# schema1.net
KiCad netlist of a schematic drawn in Altium Designer
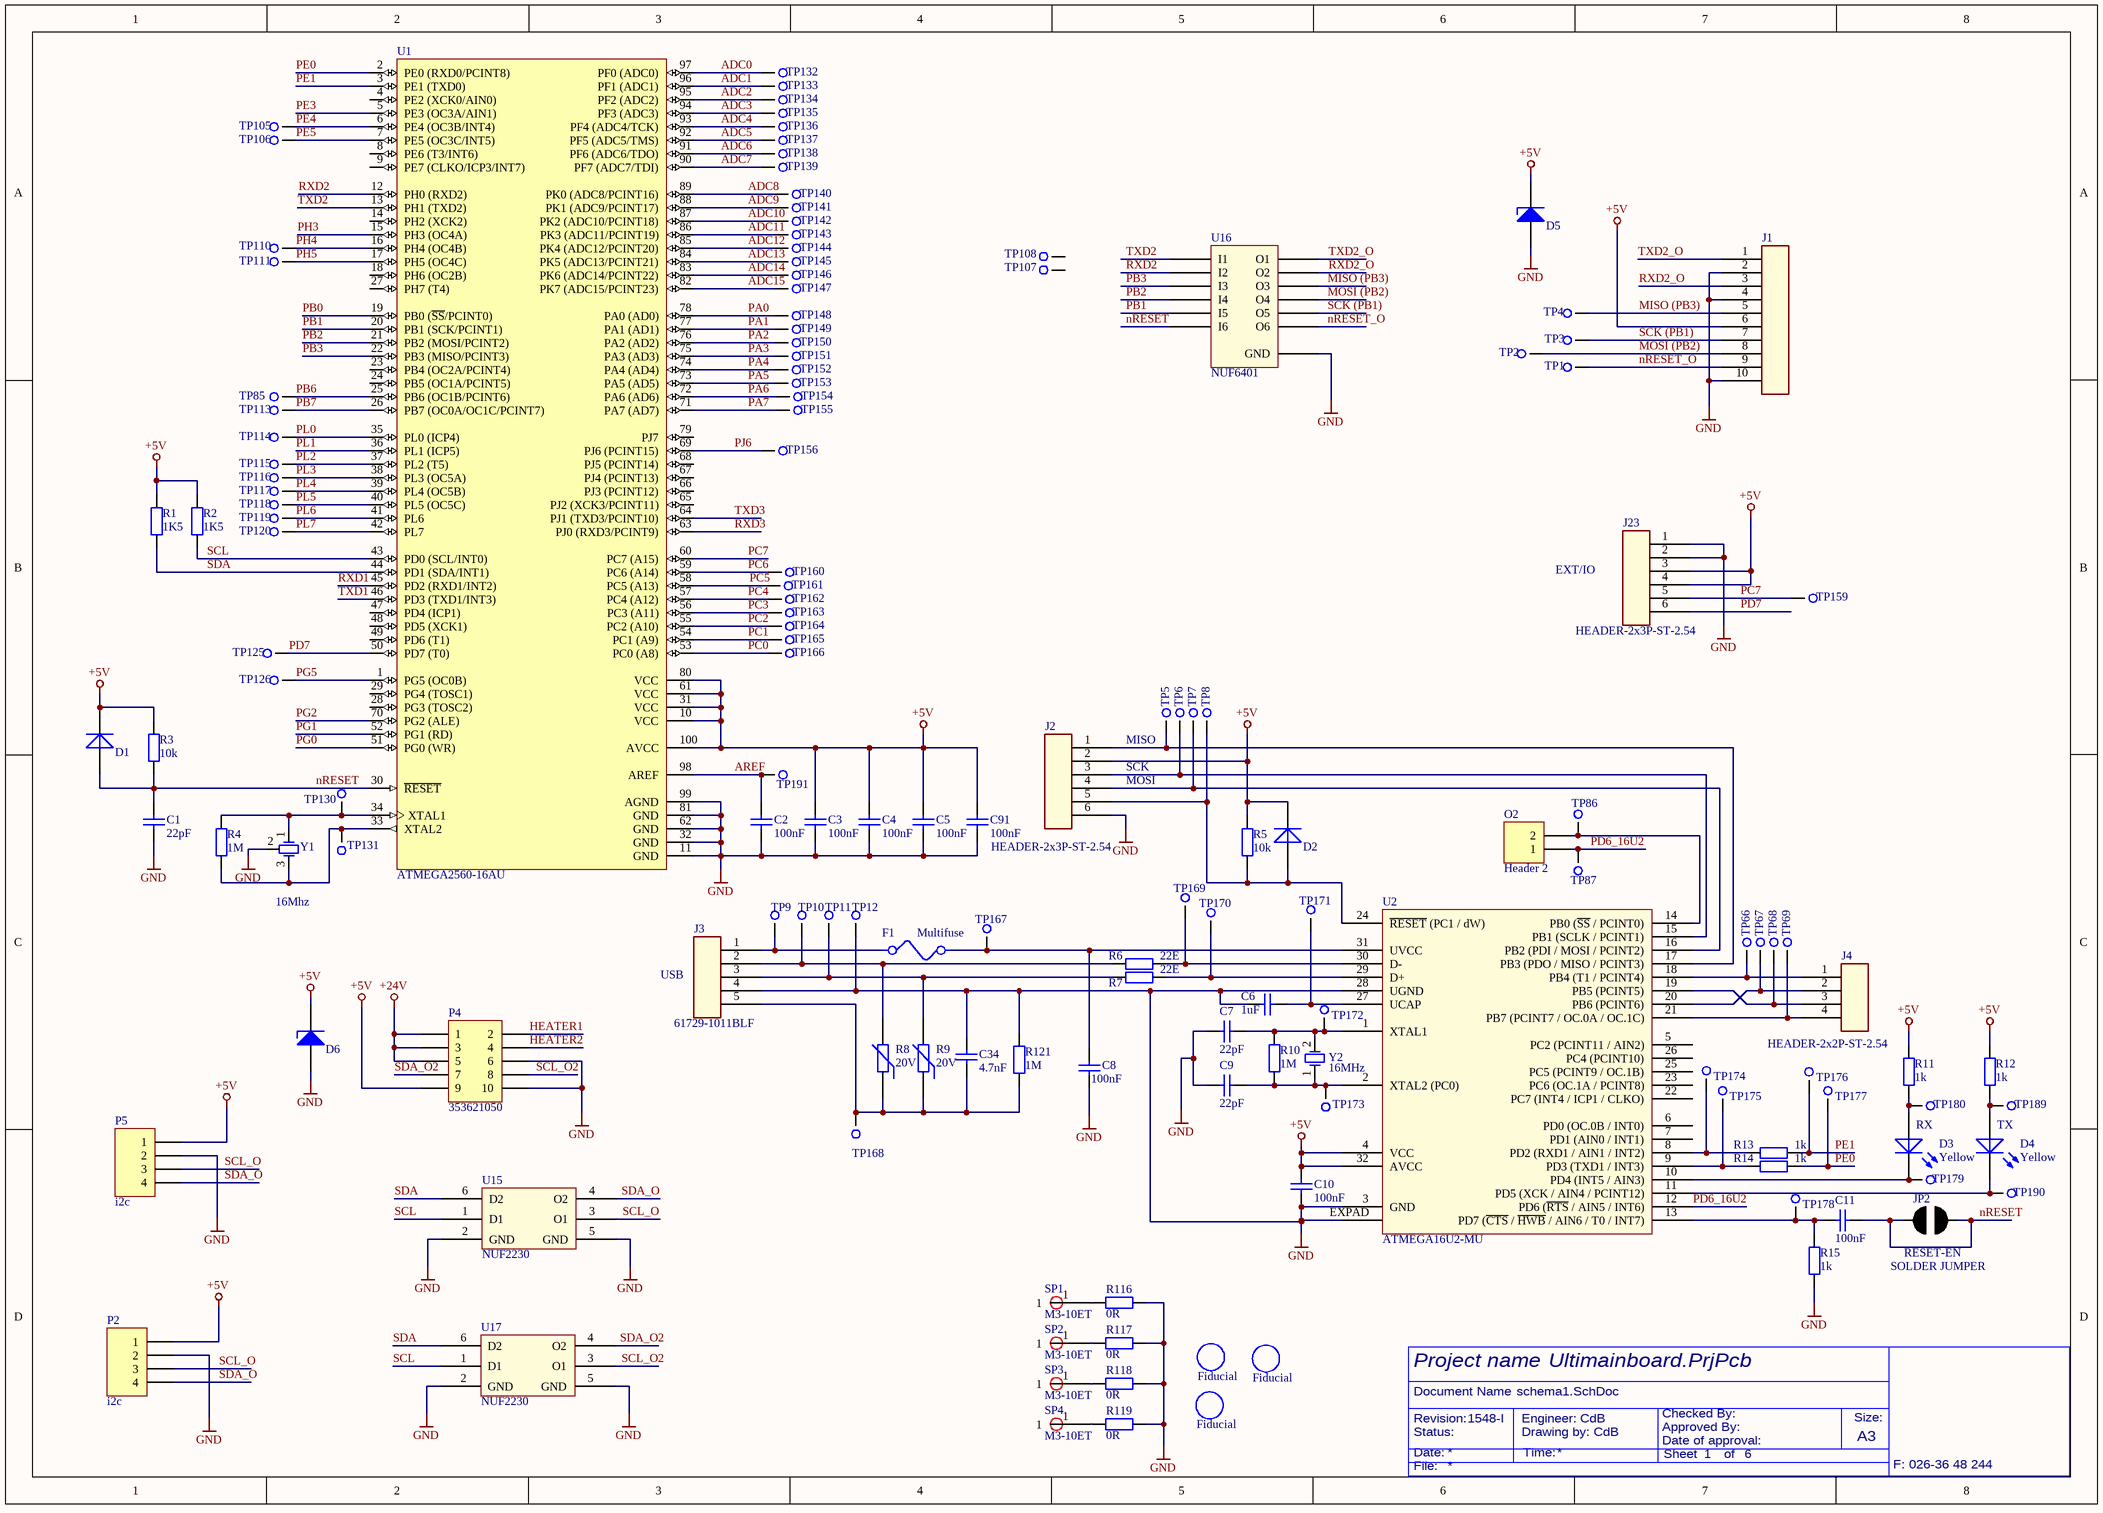
[diagram p0: schema1.SchDoc]

(export (version "E")
  (design (tool "Eeschema 10.0.6"))
  (components
    (comp (ref "C1")
      (value "22pF")
      (footprint "C0603")
      (description "RO C0G 22pF 2% 50V  0603")
      (libsource (lib "Database_Faber") (part "Capacitor"))
    )
    (comp (ref "C2")
      (value "100nF")
      (footprint "C0603")
      (description "RO X7R 100nF 10% 50V 0603")
      (libsource (lib "Database_Faber") (part "Capacitor"))
    )
    (comp (ref "C3")
      (value "100nF")
      (footprint "C0603")
      (description "RO X7R 100nF 10% 50V 0603")
      (libsource (lib "Database_Faber") (part "Capacitor"))
    )
    (comp (ref "C4")
      (value "100nF")
      (footprint "C0603")
      (description "RO X7R 100nF 10% 50V 0603")
      (libsource (lib "Database_Faber") (part "Capacitor"))
    )
    (comp (ref "C5")
      (value "100nF")
      (footprint "C0603")
      (description "RO X7R 100nF 10% 50V 0603")
      (libsource (lib "Database_Faber") (part "Capacitor"))
    )
    (comp (ref "C6")
      (value "1uF")
      (footprint "C0603")
      (description "RO X5R 1uF 10% 10V 0603")
      (libsource (lib "Database_Faber") (part "Capacitor"))
    )
    (comp (ref "C7")
      (value "22pF")
      (footprint "C0603")
      (description "RO C0G 22pF 2% 50V  0603")
      (libsource (lib "Database_Faber") (part "Capacitor"))
    )
    (comp (ref "C8")
      (value "100nF")
      (footprint "C0603")
      (description "RO X7R 100nF 10% 50V 0603")
      (libsource (lib "Database_Faber") (part "Capacitor"))
    )
    (comp (ref "C9")
      (value "22pF")
      (footprint "C0603")
      (description "RO C0G 22pF 2% 50V  0603")
      (libsource (lib "Database_Faber") (part "Capacitor"))
    )
    (comp (ref "C10")
      (value "100nF")
      (footprint "C0603")
      (description "RO X7R 100nF 10% 50V 0603")
      (libsource (lib "Database_Faber") (part "Capacitor"))
    )
    (comp (ref "C11")
      (value "100nF")
      (footprint "C0603")
      (description "RO X7R 100nF 10% 50V 0603")
      (libsource (lib "Database_Faber") (part "Capacitor"))
    )
    (comp (ref "C34")
      (value "4.7nF")
      (footprint "C0603")
      (description "RO X7R 4,7nF 10% 50V 0603")
      (fields (field (name "MFG") "MULTICOMP"))
      (libsource (lib "Database_Faber") (part "Capacitor"))
    )
    (comp (ref "C91")
      (value "100nF")
      (footprint "C0603")
      (description "RO X7R 100nF 10% 50V 0603")
      (libsource (lib "Database_Faber") (part "Capacitor"))
    )
    (comp (ref "D1")
      (value "1N4148")
      (footprint "SOD323")
      (description "RO DIODE 1N4148WS-V-GS08 SOT-323  VISHAY")
      (fields (field (name "MFG") "VISHAY"))
      (libsource (lib "Database_Faber") (part "Diode"))
    )
    (comp (ref "D2")
      (value "1N4148")
      (footprint "SOD323")
      (description "RO DIODE 1N4148WS-V-GS08 SOT-323  VISHAY")
      (fields (field (name "MFG") "VISHAY"))
      (libsource (lib "Database_Faber") (part "Diode"))
    )
    (comp (ref "D3")
      (value "Yellow")
      (footprint "LED0805-YELLOW")
      (description "RO LED GEEL HSMY-C170 0805  AVAGO")
      (fields (field (name "MFG") "AVAGO"))
      (libsource (lib "Database_Faber") (part "LED"))
    )
    (comp (ref "D4")
      (value "Yellow")
      (footprint "LED0805-YELLOW")
      (description "RO LED GEEL HSMY-C170 0805  AVAGO")
      (fields (field (name "MFG") "AVAGO"))
      (libsource (lib "Database_Faber") (part "LED"))
    )
    (comp (ref "D5")
      (value "ESD9X5.0ST5G")
      (footprint "SODFL100X40-2N")
      (description "TVS DIODE 5VWM 12.3VC SOD923")
      (fields (field (name "MFG") "ON Semiconductor"))
      (libsource (lib "Olimex interface board") (part "ESD9X5.0ST5G"))
    )
    (comp (ref "D6")
      (value "ESD9X5.0ST5G")
      (footprint "SODFL100X40-2N")
      (description "TVS DIODE 5VWM 12.3VC SOD923")
      (fields (field (name "MFG") "ON Semiconductor"))
      (libsource (lib "Olimex interface board") (part "ESD9X5.0ST5G"))
    )
    (comp (ref "F1")
      (value "Multifuse")
      (footprint "Multifuse1812")
      (description "RO ZEK MULTI 500MA SMD 1812 MF-MSMF050-2 BOURNS")
      (fields (field (name "MFG") "BOURNS"))
      (libsource (lib "Database_Faber") (part "Multifuse"))
    )
    (comp (ref "Fid1")
      (value "Fiducial")
      (footprint "Fiducial")
      (libsource (lib "Database_Faber") (part "Fiducial"))
    )
    (comp (ref "Fid2")
      (value "Fiducial")
      (footprint "Fiducial")
      (libsource (lib "Database_Faber") (part "Fiducial"))
    )
    (comp (ref "Fid3")
      (value "Fiducial")
      (footprint "Fiducial")
      (libsource (lib "Database_Faber") (part "Fiducial"))
    )
    (comp (ref "J1")
      (value "~")
      (footprint "HEADER-2X5P-ST-2.54")
      (description "header 2x5")
      (fields (field (name "MFG") "Multicomp"))
      (libsource (lib "Database_Faber") (part "HEADER 10"))
    )
    (comp (ref "J2")
      (value "HEADER-2x3P-ST-2.54")
      (footprint "HEADER-2x3P-ST-2.54")
      (description "RO CONN PR HDR 2X3P H4B-06DS-0000 INT")
      (libsource (lib "Database_Faber") (part "HEADER 6"))
    )
    (comp (ref "J3")
      (value "61729-1011BLF")
      (footprint "61729-1011BLF")
      (description "RO CONN PR USB-B HKS 61729-1011BLF FCI")
      (fields (field (name "MFG") "FCI"))
      (libsource (lib "Database_Faber") (part "HEADER 5"))
    )
    (comp (ref "J4")
      (value "HEADER-2x2P-ST-2.54")
      (footprint "HEADER-2x2P-ST-2.54")
      (description "HDR 2X2P")
      (libsource (lib "Database_Faber") (part "HEADER 4"))
    )
    (comp (ref "J23")
      (value "HEADER-2x3P-ST-2.54")
      (footprint "HEADER-2x3P-ST-2.54")
      (description "RO CONN PR HDR 2X3P H4B-06DS-0000 INT")
      (libsource (lib "Database_Faber") (part "HEADER 6"))
    )
    (comp (ref "JP2")
      (value "SOLDER JUMPER")
      (footprint "JUMPER 2 SOLDER")
      (libsource (lib "Database_Faber") (part "JUMPER 2 SOLDER"))
    )
    (comp (ref "O2")
      (value "Header 2")
      (footprint "Ultimaker:HEADER-1X2P-ST-2.54")
      (description "Header, 2-Pin")
      (fields (field (name "MFG") "MULTICOMP") (field (name "PUBLISHER") "Altium Limited"))
      (libsource (lib "Miscellaneous Connectors") (part "Header 2"))
    )
    (comp (ref "P2")
      (value "i2c")
      (footprint "B4B-XH-A")
      (description "Header, 4-Pin")
      (fields
        (field (name "MFG") "JST (JAPAN SOLDERLESS TERMINALS)")
        (field (name "PUBLISHER") "Altium Limited")
      )
      (libsource (lib "Miscellaneous Connectors") (part "Header 4"))
    )
    (comp (ref "P4")
      (value "353621050")
      (footprint "353621050")
      (description "Molex 353621050")
      (fields (field (name "MFG") "Molex"))
      (libsource (lib "Miscellaneous Connectors") (part "Header 5X2"))
    )
    (comp (ref "P5")
      (value "i2c")
      (footprint "B4B-XH-A")
      (description "Header, 4-Pin")
      (fields
        (field (name "MFG") "JST (JAPAN SOLDERLESS TERMINALS)")
        (field (name "PUBLISHER") "Altium Limited")
      )
      (libsource (lib "Miscellaneous Connectors") (part "Header 4"))
    )
    (comp (ref "R1")
      (value "1K5")
      (footprint "RESC1608X05N")
      (description "Res 1K5 0603 1% 100mW")
      (fields (field (name "MFG") "VISHAY DRALORIC"))
      (libsource (lib "altium-import") (part "root_1__Faber_SCH_lib.SchLib"))
    )
    (comp (ref "R2")
      (value "1K5")
      (footprint "RESC1608X05N")
      (description "Res 1K5 0603 1% 100mW")
      (fields (field (name "MFG") "VISHAY DRALORIC"))
      (libsource (lib "altium-import") (part "root_1__Faber_SCH_lib.SchLib"))
    )
    (comp (ref "R3")
      (value "10k")
      (footprint "R0603")
      (description "RO RES 10k0 1% 0,063W  0603")
      (libsource (lib "") (part "Resistor_2"))
    )
    (comp (ref "R4")
      (value "1M")
      (footprint "R0603")
      (description "RO RES 1M0 1% 0,1W 0603")
      (libsource (lib "") (part "Resistor_2"))
    )
    (comp (ref "R5")
      (value "10k")
      (footprint "R0603")
      (description "RO RES 10k0 1% 0,063W  0603")
      (libsource (lib "") (part "Resistor_1"))
    )
    (comp (ref "R6")
      (value "22E")
      (footprint "R0603")
      (description "RO RES 22E0 1% 0,063W 0603")
      (libsource (lib "Database_Faber") (part "Resistor"))
    )
    (comp (ref "R7")
      (value "22E")
      (footprint "R0603")
      (description "RO RES 22E0 1% 0,063W 0603")
      (libsource (lib "Database_Faber") (part "Resistor"))
    )
    (comp (ref "R8")
      (value "20V")
      (footprint "R0603")
      (description "RO VDR 0603 CG0603MLC-05E")
      (fields (field (name "MFG") "BOURNS"))
      (libsource (lib "Database_Faber") (part "Varistor"))
    )
    (comp (ref "R9")
      (value "20V")
      (footprint "R0603")
      (description "RO VDR 0603 CG0603MLC-05E")
      (fields (field (name "MFG") "BOURNS"))
      (libsource (lib "Database_Faber") (part "Varistor"))
    )
    (comp (ref "R10")
      (value "1M")
      (footprint "R0603")
      (description "RO RES 1M0 1% 0,1W 0603")
      (libsource (lib "") (part "Resistor_2"))
    )
    (comp (ref "R11")
      (value "1k")
      (footprint "R0603")
      (description "RO RES 1k0 1% 0,1W  0603")
      (libsource (lib "") (part "Resistor_2"))
    )
    (comp (ref "R12")
      (value "1k")
      (footprint "R0603")
      (description "RO RES 1k0 1% 0,1W  0603")
      (libsource (lib "") (part "Resistor_2"))
    )
    (comp (ref "R13")
      (value "1k")
      (footprint "R0603")
      (description "RO RES 1k0 1% 0,1W  0603")
      (libsource (lib "Database_Faber") (part "Resistor"))
    )
    (comp (ref "R14")
      (value "1k")
      (footprint "R0603")
      (description "RO RES 1k0 1% 0,1W  0603")
      (libsource (lib "Database_Faber") (part "Resistor"))
    )
    (comp (ref "R15")
      (value "1k")
      (footprint "R0603")
      (description "RO RES 1k0 1% 0,1W  0603")
      (libsource (lib "") (part "Resistor_1"))
    )
    (comp (ref "R116")
      (value "0R")
      (footprint "R1206")
      (description "RO RES 0R 1% 0,25W 1206")
      (fields (field (name "MFG") "VISHAY DRALORIC"))
      (libsource (lib "altium-import") (part "root_2_Resistor_"))
    )
    (comp (ref "R117")
      (value "0R")
      (footprint "R1206")
      (description "RO RES 0R 1% 0,25W 1206")
      (fields (field (name "MFG") "VISHAY DRALORIC"))
      (libsource (lib "altium-import") (part "root_2_Resistor_"))
    )
    (comp (ref "R118")
      (value "0R")
      (footprint "R1206")
      (description "RO RES 0R 1% 0,25W 1206")
      (fields (field (name "MFG") "VISHAY DRALORIC"))
      (libsource (lib "altium-import") (part "root_2_Resistor_"))
    )
    (comp (ref "R119")
      (value "0R")
      (footprint "R1206")
      (description "RO RES 0R 1% 0,25W 1206")
      (fields (field (name "MFG") "VISHAY DRALORIC"))
      (libsource (lib "altium-import") (part "root_2_Resistor_"))
    )
    (comp (ref "R121")
      (value "1M")
      (footprint "R0603")
      (description "RO RES 1M0 1% 0,1W 0603")
      (libsource (lib "") (part "Resistor_2"))
    )
    (comp (ref "SP1")
      (value "M3-10ET")
      (footprint "Spacer M3-10ET")
      (description "MOER-SMD SMTSO-M3-10ET  PEM")
      (fields (field (name "MFG") "PEM"))
      (libsource (lib "Ultimaker_1") (part "Spacer M3-10ET"))
    )
    (comp (ref "SP2")
      (value "M3-10ET")
      (footprint "Spacer M3-10ET")
      (description "MOER-SMD SMTSO-M3-10ET  PEM")
      (fields (field (name "MFG") "PEM"))
      (libsource (lib "Ultimaker_1") (part "Spacer M3-10ET"))
    )
    (comp (ref "SP3")
      (value "M3-10ET")
      (footprint "Spacer M3-10ET")
      (description "MOER-SMD SMTSO-M3-10ET  PEM")
      (fields (field (name "MFG") "PEM"))
      (libsource (lib "Ultimaker_1") (part "Spacer M3-10ET"))
    )
    (comp (ref "SP4")
      (value "M3-10ET")
      (footprint "Spacer M3-10ET")
      (description "MOER-SMD SMTSO-M3-10ET  PEM")
      (fields (field (name "MFG") "PEM"))
      (libsource (lib "Ultimaker_1") (part "Spacer M3-10ET"))
    )
    (comp (ref "TP1")
      (value "Testpoint")
      (footprint "Testpoint")
      (libsource (lib "Database_Faber") (part "Testpoint"))
    )
    (comp (ref "TP2")
      (value "Testpoint")
      (footprint "Testpoint")
      (libsource (lib "Database_Faber") (part "Testpoint"))
    )
    (comp (ref "TP3")
      (value "Testpoint")
      (footprint "Testpoint")
      (libsource (lib "Database_Faber") (part "Testpoint"))
    )
    (comp (ref "TP4")
      (value "Testpoint")
      (footprint "Testpoint")
      (libsource (lib "Database_Faber") (part "Testpoint"))
    )
    (comp (ref "TP5")
      (value "Testpoint")
      (footprint "Testpoint")
      (libsource (lib "Database_Faber") (part "Testpoint"))
    )
    (comp (ref "TP6")
      (value "Testpoint")
      (footprint "Testpoint")
      (libsource (lib "Database_Faber") (part "Testpoint"))
    )
    (comp (ref "TP7")
      (value "Testpoint")
      (footprint "Testpoint")
      (libsource (lib "Database_Faber") (part "Testpoint"))
    )
    (comp (ref "TP8")
      (value "Testpoint")
      (footprint "Testpoint")
      (libsource (lib "Database_Faber") (part "Testpoint"))
    )
    (comp (ref "TP9")
      (value "Testpoint")
      (footprint "Testpoint")
      (libsource (lib "Database_Faber") (part "Testpoint"))
    )
    (comp (ref "TP10")
      (value "Testpoint")
      (footprint "Testpoint")
      (libsource (lib "Database_Faber") (part "Testpoint"))
    )
    (comp (ref "TP11")
      (value "Testpoint")
      (footprint "Testpoint")
      (libsource (lib "Database_Faber") (part "Testpoint"))
    )
    (comp (ref "TP12")
      (value "Testpoint")
      (footprint "Testpoint")
      (libsource (lib "Database_Faber") (part "Testpoint"))
    )
    (comp (ref "TP66")
      (value "Testpoint")
      (footprint "Testpoint")
      (libsource (lib "Database_Faber") (part "Testpoint"))
    )
    (comp (ref "TP67")
      (value "Testpoint")
      (footprint "Testpoint")
      (libsource (lib "Database_Faber") (part "Testpoint"))
    )
    (comp (ref "TP68")
      (value "Testpoint")
      (footprint "Testpoint")
      (libsource (lib "Database_Faber") (part "Testpoint"))
    )
    (comp (ref "TP69")
      (value "Testpoint")
      (footprint "Testpoint")
      (libsource (lib "Database_Faber") (part "Testpoint"))
    )
    (comp (ref "TP85")
      (value "Testpoint 1.6mm")
      (footprint "Testpoint 1.6mm")
      (libsource (lib "Ultimaker") (part "Testpoint 1.6mm"))
    )
    (comp (ref "TP86")
      (value "Testpoint")
      (footprint "Testpoint")
      (libsource (lib "Database_Faber") (part "Testpoint"))
    )
    (comp (ref "TP87")
      (value "Testpoint")
      (footprint "Testpoint")
      (libsource (lib "Database_Faber") (part "Testpoint"))
    )
    (comp (ref "TP105")
      (value "Testpoint 1.6mm")
      (footprint "Testpoint 1.6mm")
      (libsource (lib "Ultimaker") (part "Testpoint 1.6mm"))
    )
    (comp (ref "TP106")
      (value "Testpoint 1.6mm")
      (footprint "Testpoint 1.6mm")
      (libsource (lib "Ultimaker") (part "Testpoint 1.6mm"))
    )
    (comp (ref "TP107")
      (value "Testpoint 1.6mm")
      (footprint "Testpoint 1.6mm")
      (libsource (lib "Ultimaker") (part "Testpoint 1.6mm"))
    )
    (comp (ref "TP108")
      (value "Testpoint 1.6mm")
      (footprint "Testpoint 1.6mm")
      (libsource (lib "Ultimaker") (part "Testpoint 1.6mm"))
    )
    (comp (ref "TP110")
      (value "Testpoint 1.6mm")
      (footprint "Testpoint 1.6mm")
      (libsource (lib "Ultimaker") (part "Testpoint 1.6mm"))
    )
    (comp (ref "TP111")
      (value "Testpoint 1.6mm")
      (footprint "Testpoint 1.6mm")
      (libsource (lib "Ultimaker") (part "Testpoint 1.6mm"))
    )
    (comp (ref "TP113")
      (value "Testpoint 1.6mm")
      (footprint "Testpoint 1.6mm")
      (libsource (lib "Ultimaker") (part "Testpoint 1.6mm"))
    )
    (comp (ref "TP114")
      (value "Testpoint 1.6mm")
      (footprint "Testpoint 1.6mm")
      (libsource (lib "Ultimaker") (part "Testpoint 1.6mm"))
    )
    (comp (ref "TP115")
      (value "Testpoint 1.6mm")
      (footprint "Testpoint 1.6mm")
      (libsource (lib "Ultimaker") (part "Testpoint 1.6mm"))
    )
    (comp (ref "TP116")
      (value "Testpoint 1.6mm")
      (footprint "Testpoint 1.6mm")
      (libsource (lib "Ultimaker") (part "Testpoint 1.6mm"))
    )
    (comp (ref "TP117")
      (value "Testpoint 1.6mm")
      (footprint "Testpoint 1.6mm")
      (libsource (lib "Ultimaker") (part "Testpoint 1.6mm"))
    )
    (comp (ref "TP118")
      (value "Testpoint 1.6mm")
      (footprint "Testpoint 1.6mm")
      (libsource (lib "Ultimaker") (part "Testpoint 1.6mm"))
    )
    (comp (ref "TP119")
      (value "Testpoint 1.6mm")
      (footprint "Testpoint 1.6mm")
      (libsource (lib "Ultimaker") (part "Testpoint 1.6mm"))
    )
    (comp (ref "TP120")
      (value "Testpoint 1.6mm")
      (footprint "Testpoint 1.6mm")
      (libsource (lib "Ultimaker") (part "Testpoint 1.6mm"))
    )
    (comp (ref "TP125")
      (value "Testpoint 1.6mm")
      (footprint "Testpoint 1.6mm")
      (libsource (lib "Ultimaker") (part "Testpoint 1.6mm"))
    )
    (comp (ref "TP126")
      (value "Testpoint 1.6mm")
      (footprint "Testpoint 1.6mm")
      (libsource (lib "Ultimaker") (part "Testpoint 1.6mm"))
    )
    (comp (ref "TP130")
      (value "Testpoint 1.6mm")
      (footprint "Testpoint 1.6mm")
      (libsource (lib "Ultimaker") (part "Testpoint 1.6mm"))
    )
    (comp (ref "TP131")
      (value "Testpoint 1.6mm")
      (footprint "Testpoint 1.6mm")
      (libsource (lib "Ultimaker") (part "Testpoint 1.6mm"))
    )
    (comp (ref "TP132")
      (value "Testpoint 1.6mm")
      (footprint "Testpoint 1.6mm")
      (libsource (lib "Ultimaker") (part "Testpoint 1.6mm"))
    )
    (comp (ref "TP133")
      (value "Testpoint 1.6mm")
      (footprint "Testpoint 1.6mm")
      (libsource (lib "Ultimaker") (part "Testpoint 1.6mm"))
    )
    (comp (ref "TP134")
      (value "Testpoint 1.6mm")
      (footprint "Testpoint 1.6mm")
      (libsource (lib "Ultimaker") (part "Testpoint 1.6mm"))
    )
    (comp (ref "TP135")
      (value "Testpoint 1.6mm")
      (footprint "Testpoint 1.6mm")
      (libsource (lib "Ultimaker") (part "Testpoint 1.6mm"))
    )
    (comp (ref "TP136")
      (value "Testpoint 1.6mm")
      (footprint "Testpoint 1.6mm")
      (libsource (lib "Ultimaker") (part "Testpoint 1.6mm"))
    )
    (comp (ref "TP137")
      (value "Testpoint 1.6mm")
      (footprint "Testpoint 1.6mm")
      (libsource (lib "Ultimaker") (part "Testpoint 1.6mm"))
    )
    (comp (ref "TP138")
      (value "Testpoint 1.6mm")
      (footprint "Testpoint 1.6mm")
      (libsource (lib "Ultimaker") (part "Testpoint 1.6mm"))
    )
    (comp (ref "TP139")
      (value "Testpoint 1.6mm")
      (footprint "Testpoint 1.6mm")
      (libsource (lib "Ultimaker") (part "Testpoint 1.6mm"))
    )
    (comp (ref "TP140")
      (value "Testpoint 1.6mm")
      (footprint "Testpoint 1.6mm")
      (libsource (lib "Ultimaker") (part "Testpoint 1.6mm"))
    )
    (comp (ref "TP141")
      (value "Testpoint 1.6mm")
      (footprint "Testpoint 1.6mm")
      (libsource (lib "Ultimaker") (part "Testpoint 1.6mm"))
    )
    (comp (ref "TP142")
      (value "Testpoint 1.6mm")
      (footprint "Testpoint 1.6mm")
      (libsource (lib "Ultimaker") (part "Testpoint 1.6mm"))
    )
    (comp (ref "TP143")
      (value "Testpoint 1.6mm")
      (footprint "Testpoint 1.6mm")
      (libsource (lib "Ultimaker") (part "Testpoint 1.6mm"))
    )
    (comp (ref "TP144")
      (value "Testpoint 1.6mm")
      (footprint "Testpoint 1.6mm")
      (libsource (lib "Ultimaker") (part "Testpoint 1.6mm"))
    )
    (comp (ref "TP145")
      (value "Testpoint 1.6mm")
      (footprint "Testpoint 1.6mm")
      (libsource (lib "Ultimaker") (part "Testpoint 1.6mm"))
    )
    (comp (ref "TP146")
      (value "Testpoint 1.6mm")
      (footprint "Testpoint 1.6mm")
      (libsource (lib "Ultimaker") (part "Testpoint 1.6mm"))
    )
    (comp (ref "TP147")
      (value "Testpoint 1.6mm")
      (footprint "Testpoint 1.6mm")
      (libsource (lib "Ultimaker") (part "Testpoint 1.6mm"))
    )
    (comp (ref "TP148")
      (value "Testpoint 1.6mm")
      (footprint "Testpoint 1.6mm")
      (libsource (lib "Ultimaker") (part "Testpoint 1.6mm"))
    )
    (comp (ref "TP149")
      (value "Testpoint 1.6mm")
      (footprint "Testpoint 1.6mm")
      (libsource (lib "Ultimaker") (part "Testpoint 1.6mm"))
    )
    (comp (ref "TP150")
      (value "Testpoint 1.6mm")
      (footprint "Testpoint 1.6mm")
      (libsource (lib "Ultimaker") (part "Testpoint 1.6mm"))
    )
    (comp (ref "TP151")
      (value "Testpoint 1.6mm")
      (footprint "Testpoint 1.6mm")
      (libsource (lib "Ultimaker") (part "Testpoint 1.6mm"))
    )
    (comp (ref "TP152")
      (value "Testpoint 1.6mm")
      (footprint "Testpoint 1.6mm")
      (libsource (lib "Ultimaker") (part "Testpoint 1.6mm"))
    )
    (comp (ref "TP153")
      (value "Testpoint 1.6mm")
      (footprint "Testpoint 1.6mm")
      (libsource (lib "Ultimaker") (part "Testpoint 1.6mm"))
    )
    (comp (ref "TP154")
      (value "Testpoint 1.6mm")
      (footprint "Testpoint 1.6mm")
      (libsource (lib "Ultimaker") (part "Testpoint 1.6mm"))
    )
    (comp (ref "TP155")
      (value "Testpoint 1.6mm")
      (footprint "Testpoint 1.6mm")
      (libsource (lib "Ultimaker") (part "Testpoint 1.6mm"))
    )
    (comp (ref "TP156")
      (value "Testpoint 1.6mm")
      (footprint "Testpoint 1.6mm")
      (libsource (lib "Ultimaker") (part "Testpoint 1.6mm"))
    )
    (comp (ref "TP159")
      (value "Testpoint 1.6mm")
      (footprint "Testpoint 1.6mm")
      (libsource (lib "Ultimaker") (part "Testpoint 1.6mm"))
    )
    (comp (ref "TP160")
      (value "Testpoint 1.6mm")
      (footprint "Testpoint 1.6mm")
      (libsource (lib "Ultimaker") (part "Testpoint 1.6mm"))
    )
    (comp (ref "TP161")
      (value "Testpoint 1.6mm")
      (footprint "Testpoint 1.6mm")
      (libsource (lib "Ultimaker") (part "Testpoint 1.6mm"))
    )
    (comp (ref "TP162")
      (value "Testpoint 1.6mm")
      (footprint "Testpoint 1.6mm")
      (libsource (lib "Ultimaker") (part "Testpoint 1.6mm"))
    )
    (comp (ref "TP163")
      (value "Testpoint 1.6mm")
      (footprint "Testpoint 1.6mm")
      (libsource (lib "Ultimaker") (part "Testpoint 1.6mm"))
    )
    (comp (ref "TP164")
      (value "Testpoint 1.6mm")
      (footprint "Testpoint 1.6mm")
      (libsource (lib "Ultimaker") (part "Testpoint 1.6mm"))
    )
    (comp (ref "TP165")
      (value "Testpoint 1.6mm")
      (footprint "Testpoint 1.6mm")
      (libsource (lib "Ultimaker") (part "Testpoint 1.6mm"))
    )
    (comp (ref "TP166")
      (value "Testpoint 1.6mm")
      (footprint "Testpoint 1.6mm")
      (libsource (lib "Ultimaker") (part "Testpoint 1.6mm"))
    )
    (comp (ref "TP167")
      (value "Testpoint 1.6mm")
      (footprint "Testpoint 1.6mm")
      (libsource (lib "Ultimaker") (part "Testpoint 1.6mm"))
    )
    (comp (ref "TP168")
      (value "Testpoint 1.6mm")
      (footprint "Testpoint 1.6mm")
      (libsource (lib "Ultimaker") (part "Testpoint 1.6mm"))
    )
    (comp (ref "TP169")
      (value "Testpoint 1.6mm")
      (footprint "Testpoint 1.6mm")
      (libsource (lib "Ultimaker") (part "Testpoint 1.6mm"))
    )
    (comp (ref "TP170")
      (value "Testpoint 1.6mm")
      (footprint "Testpoint 1.6mm")
      (libsource (lib "Ultimaker") (part "Testpoint 1.6mm"))
    )
    (comp (ref "TP171")
      (value "Testpoint 1.6mm")
      (footprint "Testpoint 1.6mm")
      (libsource (lib "Ultimaker") (part "Testpoint 1.6mm"))
    )
    (comp (ref "TP172")
      (value "Testpoint 1.6mm")
      (footprint "Testpoint 1.6mm")
      (libsource (lib "Ultimaker") (part "Testpoint 1.6mm"))
    )
    (comp (ref "TP173")
      (value "Testpoint 1.6mm")
      (footprint "Testpoint 1.6mm")
      (libsource (lib "Ultimaker") (part "Testpoint 1.6mm"))
    )
    (comp (ref "TP174")
      (value "Testpoint 1.6mm")
      (footprint "Testpoint 1.6mm")
      (libsource (lib "Ultimaker") (part "Testpoint 1.6mm"))
    )
    (comp (ref "TP175")
      (value "Testpoint 1.6mm")
      (footprint "Testpoint 1.6mm")
      (libsource (lib "Ultimaker") (part "Testpoint 1.6mm"))
    )
    (comp (ref "TP176")
      (value "Testpoint 1.6mm")
      (footprint "Testpoint 1.6mm")
      (libsource (lib "Ultimaker") (part "Testpoint 1.6mm"))
    )
    (comp (ref "TP177")
      (value "Testpoint 1.6mm")
      (footprint "Testpoint 1.6mm")
      (libsource (lib "Ultimaker") (part "Testpoint 1.6mm"))
    )
    (comp (ref "TP178")
      (value "Testpoint 1.6mm")
      (footprint "Testpoint 1.6mm")
      (libsource (lib "Ultimaker") (part "Testpoint 1.6mm"))
    )
    (comp (ref "TP179")
      (value "Testpoint 1.6mm")
      (footprint "Testpoint 1.6mm")
      (libsource (lib "Ultimaker") (part "Testpoint 1.6mm"))
    )
    (comp (ref "TP180")
      (value "Testpoint 1.6mm")
      (footprint "Testpoint 1.6mm")
      (libsource (lib "Ultimaker") (part "Testpoint 1.6mm"))
    )
    (comp (ref "TP189")
      (value "Testpoint 1.6mm")
      (footprint "Testpoint 1.6mm")
      (libsource (lib "Ultimaker") (part "Testpoint 1.6mm"))
    )
    (comp (ref "TP190")
      (value "Testpoint 1.6mm")
      (footprint "Testpoint 1.6mm")
      (libsource (lib "Ultimaker") (part "Testpoint 1.6mm"))
    )
    (comp (ref "TP191")
      (value "Testpoint 1.6mm")
      (footprint "Testpoint 1.6mm")
      (libsource (lib "Ultimaker") (part "Testpoint 1.6mm"))
    )
    (comp (ref "U1")
      (value "ATMEGA2560-16AU")
      (footprint "TSQFP50P1600X1600X120-100N")
      (description "RO IC ATMEGA2560-16AU TQFP-100 ATMEL")
      (fields (field (name "MFG") "Atmel"))
      (libsource (lib "Database_Faber") (part "ATmega2560-16AU"))
    )
    (comp (ref "U2")
      (value "ATMEGA16U2-MU")
      (footprint "QFN50P500X500X100-32-EX")
      (description "RO IC ATMEGA16U2-MU QFN-32 ATMEL")
      (fields (field (name "MFG") "Atmel"))
      (libsource (lib "Database_Faber") (part "ATMEGA16U2-MU"))
    )
    (comp (ref "U15")
      (value "NUF2230")
      (footprint "SOTFL50P160X60-6N")
      (fields (field (name "MFG") "ON Semiconductor"))
      (libsource (lib "printehead") (part "NUF2230"))
    )
    (comp (ref "U16")
      (value "NUF6401")
      (footprint "SON50P140X100_HS-13N")
      (fields (field (name "MFG") "ON Semiconductor"))
      (libsource (lib "UltiController") (part "NUF6401"))
    )
    (comp (ref "U17")
      (value "NUF2230")
      (footprint "SOTFL50P160X60-6N")
      (fields (field (name "MFG") "ON Semiconductor"))
      (libsource (lib "printehead") (part "NUF2230"))
    )
    (comp (ref "Y1")
      (value "16Mhz")
      (footprint "CSTC")
      (description "RO KRIS 16MHz CSTCE16M0V53-R0 SMD MURATA")
      (fields (field (name "MFG") "MURATA"))
      (libsource (lib "Database_Faber") (part "XTAL-3"))
    )
    (comp (ref "Y2")
      (value "16MHz")
      (footprint "XT49M-2016M")
      (description "RO KRISTAL 16.0MHz  HC49/4HSMX  SMD CMAC")
      (fields (field (name "MFG") "CMAC"))
      (libsource (lib "Database_Faber") (part "XTAL-2"))
    )
  )
  (nets
    (net (code "1") (name "+5V") (class "Default")
      (node (ref "C10") (pin "2") (pinfunction "2_2") (pintype "passive"))
      (node (ref "C3") (pin "2") (pinfunction "2_2") (pintype "passive"))
      (node (ref "C4") (pin "2") (pinfunction "2_2") (pintype "passive"))
      (node (ref "C5") (pin "2") (pinfunction "2_2") (pintype "passive"))
      (node (ref "C91") (pin "2") (pinfunction "2_2") (pintype "passive"))
      (node (ref "D1") (pin "2") (pinfunction "K_2") (pintype "passive"))
      (node (ref "D2") (pin "2") (pinfunction "K_2") (pintype "passive"))
      (node (ref "D5") (pin "1") (pinfunction "K_1") (pintype "passive"))
      (node (ref "D6") (pin "1") (pinfunction "K_1") (pintype "passive"))
      (node (ref "J1") (pin "6") (pinfunction "6_6") (pintype "passive"))
      (node (ref "J2") (pin "2") (pinfunction "2_2") (pintype "passive"))
      (node (ref "J23") (pin "3") (pinfunction "3_3") (pintype "passive"))
      (node (ref "J23") (pin "4") (pinfunction "4_4") (pintype "passive"))
      (node (ref "P2") (pin "1") (pinfunction "1_1") (pintype "passive"))
      (node (ref "P4") (pin "9") (pinfunction "9_9") (pintype "passive"))
      (node (ref "P5") (pin "1") (pinfunction "1_1") (pintype "passive"))
      (node (ref "R1") (pin "2") (pinfunction "2_2") (pintype "passive"))
      (node (ref "R11") (pin "2") (pinfunction "2_2") (pintype "passive"))
      (node (ref "R12") (pin "2") (pinfunction "2_2") (pintype "passive"))
      (node (ref "R2") (pin "2") (pinfunction "2_2") (pintype "passive"))
      (node (ref "R3") (pin "2") (pinfunction "2_2") (pintype "passive"))
      (node (ref "R5") (pin "1") (pinfunction "1_1") (pintype "passive"))
      (node (ref "U1") (pin "10") (pinfunction "VCC_10") (pintype "power_in"))
      (node (ref "U1") (pin "100") (pinfunction "AVCC_100") (pintype "power_in"))
      (node (ref "U1") (pin "31") (pinfunction "VCC_31") (pintype "power_in"))
      (node (ref "U1") (pin "61") (pinfunction "VCC_61") (pintype "power_in"))
      (node (ref "U1") (pin "80") (pinfunction "VCC_80") (pintype "power_in"))
      (node (ref "U2") (pin "32") (pinfunction "AVCC_32") (pintype "passive"))
      (node (ref "U2") (pin "4") (pinfunction "VCC_4") (pintype "passive"))
    )
    (net (code "2") (name "+24V") (class "Default")
      (node (ref "P4") (pin "1") (pinfunction "1_1") (pintype "passive"))
      (node (ref "P4") (pin "3") (pinfunction "3_3") (pintype "passive"))
      (node (ref "P4") (pin "5") (pinfunction "5_5") (pintype "passive"))
    )
    (net (code "3") (name "/ADC0") (class "Default")
      (node (ref "TP132") (pin "1") (pinfunction "1_1") (pintype "passive"))
      (node (ref "U1") (pin "97") (pinfunction "PF0_(ADC0)_97") (pintype "bidirectional"))
    )
    (net (code "4") (name "/ADC1") (class "Default")
      (node (ref "TP133") (pin "1") (pinfunction "1_1") (pintype "passive"))
      (node (ref "U1") (pin "96") (pinfunction "PF1_(ADC1)_96") (pintype "bidirectional"))
    )
    (net (code "5") (name "/ADC2") (class "Default")
      (node (ref "TP134") (pin "1") (pinfunction "1_1") (pintype "passive"))
      (node (ref "U1") (pin "95") (pinfunction "PF2_(ADC2)_95") (pintype "bidirectional"))
    )
    (net (code "6") (name "/ADC3") (class "Default")
      (node (ref "TP135") (pin "1") (pinfunction "1_1") (pintype "passive"))
      (node (ref "U1") (pin "94") (pinfunction "PF3_(ADC3)_94") (pintype "bidirectional"))
    )
    (net (code "7") (name "/ADC4") (class "Default")
      (node (ref "TP136") (pin "1") (pinfunction "1_1") (pintype "passive"))
      (node (ref "U1") (pin "93") (pinfunction "PF4_(ADC4/TCK)_93") (pintype "bidirectional"))
    )
    (net (code "8") (name "/ADC5") (class "Default")
      (node (ref "TP137") (pin "1") (pinfunction "1_1") (pintype "passive"))
      (node (ref "U1") (pin "92") (pinfunction "PF5_(ADC5/TMS)_92") (pintype "bidirectional"))
    )
    (net (code "9") (name "/ADC6") (class "Default")
      (node (ref "TP138") (pin "1") (pinfunction "1_1") (pintype "passive"))
      (node (ref "U1") (pin "91") (pinfunction "PF6_(ADC6/TDO)_91") (pintype "bidirectional"))
    )
    (net (code "10") (name "/ADC7") (class "Default")
      (node (ref "TP139") (pin "1") (pinfunction "1_1") (pintype "passive"))
      (node (ref "U1") (pin "90") (pinfunction "PF7_(ADC7/TDI)_90") (pintype "bidirectional"))
    )
    (net (code "11") (name "/ADC8") (class "Default")
      (node (ref "TP140") (pin "1") (pinfunction "1_1") (pintype "passive"))
      (node (ref "U1") (pin "89") (pinfunction "PK0_(ADC8/PCINT16)_89") (pintype "bidirectional"))
    )
    (net (code "12") (name "/ADC9") (class "Default")
      (node (ref "TP141") (pin "1") (pinfunction "1_1") (pintype "passive"))
      (node (ref "U1") (pin "88") (pinfunction "PK1_(ADC9/PCINT17)_88") (pintype "bidirectional"))
    )
    (net (code "13") (name "/ADC10") (class "Default")
      (node (ref "TP142") (pin "1") (pinfunction "1_1") (pintype "passive"))
      (node (ref "U1") (pin "87") (pinfunction "PK2_(ADC10/PCINT18)_87") (pintype "bidirectional"))
    )
    (net (code "14") (name "/ADC11") (class "Default")
      (node (ref "TP143") (pin "1") (pinfunction "1_1") (pintype "passive"))
      (node (ref "U1") (pin "86") (pinfunction "PK3_(ADC11/PCINT19)_86") (pintype "bidirectional"))
    )
    (net (code "15") (name "/ADC12") (class "Default")
      (node (ref "TP144") (pin "1") (pinfunction "1_1") (pintype "passive"))
      (node (ref "U1") (pin "85") (pinfunction "PK4_(ADC12/PCINT20)_85") (pintype "bidirectional"))
    )
    (net (code "16") (name "/ADC13") (class "Default")
      (node (ref "TP145") (pin "1") (pinfunction "1_1") (pintype "passive"))
      (node (ref "U1") (pin "84") (pinfunction "PK5_(ADC13/PCINT21)_84") (pintype "bidirectional"))
    )
    (net (code "17") (name "/ADC14") (class "Default")
      (node (ref "TP146") (pin "1") (pinfunction "1_1") (pintype "passive"))
      (node (ref "U1") (pin "83") (pinfunction "PK6_(ADC14/PCINT22)_83") (pintype "bidirectional"))
    )
    (net (code "18") (name "/ADC15") (class "Default")
      (node (ref "TP147") (pin "1") (pinfunction "1_1") (pintype "passive"))
      (node (ref "U1") (pin "82") (pinfunction "PK7_(ADC15/PCINT23)_82") (pintype "bidirectional"))
    )
    (net (code "19") (name "/AREF") (class "Default")
      (node (ref "C2") (pin "2") (pinfunction "2_2") (pintype "passive"))
      (node (ref "TP191") (pin "1") (pinfunction "1_1") (pintype "passive"))
      (node (ref "U1") (pin "98") (pinfunction "AREF_98") (pintype "power_in"))
    )
    (net (code "20") (name "/HEATER1") (class "Default")
      (node (ref "P4") (pin "2") (pinfunction "2_2") (pintype "passive"))
    )
    (net (code "21") (name "/HEATER2") (class "Default")
      (node (ref "P4") (pin "4") (pinfunction "4_4") (pintype "passive"))
    )
    (net (code "22") (name "/MISO (PB3)") (class "Default")
      (node (ref "J1") (pin "5") (pinfunction "5_5") (pintype "passive"))
      (node (ref "TP4") (pin "1") (pinfunction "1_1") (pintype "passive"))
      (node (ref "U16") (pin "10") (pinfunction "O3_10") (pintype "passive"))
    )
    (net (code "23") (name "/MOSI (PB2)") (class "Default")
      (node (ref "J1") (pin "8") (pinfunction "8_8") (pintype "passive"))
      (node (ref "TP2") (pin "1") (pinfunction "1_1") (pintype "passive"))
      (node (ref "U16") (pin "9") (pinfunction "O4_9") (pintype "passive"))
    )
    (net (code "24") (name "/PA0") (class "Default")
      (node (ref "TP148") (pin "1") (pinfunction "1_1") (pintype "passive"))
      (node (ref "U1") (pin "78") (pinfunction "PA0_(AD0)_78") (pintype "bidirectional"))
    )
    (net (code "25") (name "/PA1") (class "Default")
      (node (ref "TP149") (pin "1") (pinfunction "1_1") (pintype "passive"))
      (node (ref "U1") (pin "77") (pinfunction "PA1_(AD1)_77") (pintype "bidirectional"))
    )
    (net (code "26") (name "/PA2") (class "Default")
      (node (ref "TP150") (pin "1") (pinfunction "1_1") (pintype "passive"))
      (node (ref "U1") (pin "76") (pinfunction "PA2_(AD2)_76") (pintype "bidirectional"))
    )
    (net (code "27") (name "/PA3") (class "Default")
      (node (ref "TP151") (pin "1") (pinfunction "1_1") (pintype "passive"))
      (node (ref "U1") (pin "75") (pinfunction "PA3_(AD3)_75") (pintype "bidirectional"))
    )
    (net (code "28") (name "/PA4") (class "Default")
      (node (ref "TP152") (pin "1") (pinfunction "1_1") (pintype "passive"))
      (node (ref "U1") (pin "74") (pinfunction "PA4_(AD4)_74") (pintype "bidirectional"))
    )
    (net (code "29") (name "/PA5") (class "Default")
      (node (ref "TP153") (pin "1") (pinfunction "1_1") (pintype "passive"))
      (node (ref "U1") (pin "73") (pinfunction "PA5_(AD5)_73") (pintype "bidirectional"))
    )
    (net (code "30") (name "/PA6") (class "Default")
      (node (ref "TP154") (pin "1") (pinfunction "1_1") (pintype "passive"))
      (node (ref "U1") (pin "72") (pinfunction "PA6_(AD6)_72") (pintype "bidirectional"))
    )
    (net (code "31") (name "/PA7") (class "Default")
      (node (ref "TP155") (pin "1") (pinfunction "1_1") (pintype "passive"))
      (node (ref "U1") (pin "71") (pinfunction "PA7_(AD7)_71") (pintype "bidirectional"))
    )
    (net (code "32") (name "/PB0") (class "Default")
      (node (ref "U1") (pin "19") (pinfunction "PB0_(~{SS}/PCINT0)_19") (pintype "bidirectional"))
    )
    (net (code "33") (name "/PB1") (class "Default")
      (node (ref "U1") (pin "20") (pinfunction "PB1_(SCK/PCINT1)_20") (pintype "bidirectional"))
      (node (ref "U16") (pin "5") (pinfunction "I5_5") (pintype "passive"))
    )
    (net (code "34") (name "/PB2") (class "Default")
      (node (ref "U1") (pin "21") (pinfunction "PB2_(MOSI/PCINT2)_21") (pintype "bidirectional"))
      (node (ref "U16") (pin "4") (pinfunction "I4_4") (pintype "passive"))
    )
    (net (code "35") (name "/PB3") (class "Default")
      (node (ref "U1") (pin "22") (pinfunction "PB3_(MISO/PCINT3)_22") (pintype "bidirectional"))
      (node (ref "U16") (pin "3") (pinfunction "I3_3") (pintype "passive"))
    )
    (net (code "36") (name "/PB6") (class "Default")
      (node (ref "TP85") (pin "1") (pinfunction "1_1") (pintype "passive"))
      (node (ref "U1") (pin "25") (pinfunction "PB6_(OC1B/PCINT6)_25") (pintype "bidirectional"))
    )
    (net (code "37") (name "/PB7") (class "Default")
      (node (ref "TP113") (pin "1") (pinfunction "1_1") (pintype "passive"))
      (node (ref "U1") (pin "26") (pinfunction "PB7_(OC0A/OC1C/PCINT7)_26") (pintype "bidirectional"))
    )
    (net (code "38") (name "/PC0") (class "Default")
      (node (ref "TP166") (pin "1") (pinfunction "1_1") (pintype "passive"))
      (node (ref "U1") (pin "53") (pinfunction "PC0_(A8)_53") (pintype "bidirectional"))
    )
    (net (code "39") (name "/PC1") (class "Default")
      (node (ref "TP165") (pin "1") (pinfunction "1_1") (pintype "passive"))
      (node (ref "U1") (pin "54") (pinfunction "PC1_(A9)_54") (pintype "bidirectional"))
    )
    (net (code "40") (name "/PC2") (class "Default")
      (node (ref "TP164") (pin "1") (pinfunction "1_1") (pintype "passive"))
      (node (ref "U1") (pin "55") (pinfunction "PC2_(A10)_55") (pintype "bidirectional"))
    )
    (net (code "41") (name "/PC3") (class "Default")
      (node (ref "TP163") (pin "1") (pinfunction "1_1") (pintype "passive"))
      (node (ref "U1") (pin "56") (pinfunction "PC3_(A11)_56") (pintype "bidirectional"))
    )
    (net (code "42") (name "/PC4") (class "Default")
      (node (ref "TP162") (pin "1") (pinfunction "1_1") (pintype "passive"))
      (node (ref "U1") (pin "57") (pinfunction "PC4_(A12)_57") (pintype "bidirectional"))
    )
    (net (code "43") (name "/PC5") (class "Default")
      (node (ref "TP161") (pin "1") (pinfunction "1_1") (pintype "passive"))
      (node (ref "U1") (pin "58") (pinfunction "PC5_(A13)_58") (pintype "bidirectional"))
    )
    (net (code "44") (name "/PC6") (class "Default")
      (node (ref "TP160") (pin "1") (pinfunction "1_1") (pintype "passive"))
      (node (ref "U1") (pin "59") (pinfunction "PC6_(A14)_59") (pintype "bidirectional"))
    )
    (net (code "45") (name "/PC7") (class "Default")
      (node (ref "J23") (pin "5") (pinfunction "5_5") (pintype "passive"))
      (node (ref "TP159") (pin "1") (pinfunction "1_1") (pintype "passive"))
      (node (ref "U1") (pin "60") (pinfunction "PC7_(A15)_60") (pintype "bidirectional"))
    )
    (net (code "46") (name "/PD6_16U2") (class "Default")
      (node (ref "O2") (pin "1") (pinfunction "1_1") (pintype "passive"))
      (node (ref "TP87") (pin "1") (pinfunction "1_1") (pintype "passive"))
      (node (ref "U2") (pin "12") (pinfunction "PD6_(~{RTS}_/_AIN5_/_INT6)_12") (pintype "passive"))
    )
    (net (code "47") (name "/PD7") (class "Default")
      (node (ref "J23") (pin "6") (pinfunction "6_6") (pintype "passive"))
      (node (ref "TP125") (pin "1") (pinfunction "1_1") (pintype "passive"))
      (node (ref "U1") (pin "50") (pinfunction "PD7_(T0)_50") (pintype "bidirectional"))
    )
    (net (code "48") (name "/PE0") (class "Default")
      (node (ref "R14") (pin "2") (pinfunction "2_2") (pintype "passive"))
      (node (ref "TP177") (pin "1") (pinfunction "1_1") (pintype "passive"))
      (node (ref "U1") (pin "2") (pinfunction "PE0_(RXD0/PCINT8)_2") (pintype "bidirectional"))
    )
    (net (code "49") (name "/PE1") (class "Default")
      (node (ref "R13") (pin "2") (pinfunction "2_2") (pintype "passive"))
      (node (ref "TP176") (pin "1") (pinfunction "1_1") (pintype "passive"))
      (node (ref "U1") (pin "3") (pinfunction "PE1_(TXD0)_3") (pintype "bidirectional"))
    )
    (net (code "50") (name "/PE3") (class "Default")
      (node (ref "U1") (pin "5") (pinfunction "PE3_(OC3A/AIN1)_5") (pintype "bidirectional"))
    )
    (net (code "51") (name "/PE4") (class "Default")
      (node (ref "TP105") (pin "1") (pinfunction "1_1") (pintype "passive"))
      (node (ref "U1") (pin "6") (pinfunction "PE4_(OC3B/INT4)_6") (pintype "bidirectional"))
    )
    (net (code "52") (name "/PE5") (class "Default")
      (node (ref "TP106") (pin "1") (pinfunction "1_1") (pintype "passive"))
      (node (ref "U1") (pin "7") (pinfunction "PE5_(OC3C/INT5)_7") (pintype "bidirectional"))
    )
    (net (code "53") (name "/PG0") (class "Default")
      (node (ref "U1") (pin "51") (pinfunction "PG0_(WR)_51") (pintype "bidirectional"))
    )
    (net (code "54") (name "/PG1") (class "Default")
      (node (ref "U1") (pin "52") (pinfunction "PG1_(RD)_52") (pintype "bidirectional"))
    )
    (net (code "55") (name "/PG2") (class "Default")
      (node (ref "U1") (pin "70") (pinfunction "PG2_(ALE)_70") (pintype "bidirectional"))
    )
    (net (code "56") (name "/PG5") (class "Default")
      (node (ref "TP126") (pin "1") (pinfunction "1_1") (pintype "passive"))
      (node (ref "U1") (pin "1") (pinfunction "PG5_(OC0B)_1") (pintype "bidirectional"))
    )
    (net (code "57") (name "/PH3") (class "Default")
      (node (ref "U1") (pin "15") (pinfunction "PH3_(OC4A)_15") (pintype "bidirectional"))
    )
    (net (code "58") (name "/PH4") (class "Default")
      (node (ref "TP110") (pin "1") (pinfunction "1_1") (pintype "passive"))
      (node (ref "U1") (pin "16") (pinfunction "PH4_(OC4B)_16") (pintype "bidirectional"))
    )
    (net (code "59") (name "/PH5") (class "Default")
      (node (ref "TP111") (pin "1") (pinfunction "1_1") (pintype "passive"))
      (node (ref "U1") (pin "17") (pinfunction "PH5_(OC4C)_17") (pintype "bidirectional"))
    )
    (net (code "60") (name "/PJ6") (class "Default")
      (node (ref "TP156") (pin "1") (pinfunction "1_1") (pintype "passive"))
      (node (ref "U1") (pin "69") (pinfunction "PJ6_(PCINT15)_69") (pintype "bidirectional"))
    )
    (net (code "61") (name "/PL0") (class "Default")
      (node (ref "TP114") (pin "1") (pinfunction "1_1") (pintype "passive"))
      (node (ref "U1") (pin "35") (pinfunction "PL0_(ICP4)_35") (pintype "bidirectional"))
    )
    (net (code "62") (name "/PL1") (class "Default")
      (node (ref "U1") (pin "36") (pinfunction "PL1_(ICP5)_36") (pintype "bidirectional"))
    )
    (net (code "63") (name "/PL2") (class "Default")
      (node (ref "TP115") (pin "1") (pinfunction "1_1") (pintype "passive"))
      (node (ref "U1") (pin "37") (pinfunction "PL2_(T5)_37") (pintype "bidirectional"))
    )
    (net (code "64") (name "/PL3") (class "Default")
      (node (ref "TP116") (pin "1") (pinfunction "1_1") (pintype "passive"))
      (node (ref "U1") (pin "38") (pinfunction "PL3_(OC5A)_38") (pintype "bidirectional"))
    )
    (net (code "65") (name "/PL4") (class "Default")
      (node (ref "TP117") (pin "1") (pinfunction "1_1") (pintype "passive"))
      (node (ref "U1") (pin "39") (pinfunction "PL4_(OC5B)_39") (pintype "bidirectional"))
    )
    (net (code "66") (name "/PL5") (class "Default")
      (node (ref "TP118") (pin "1") (pinfunction "1_1") (pintype "passive"))
      (node (ref "U1") (pin "40") (pinfunction "PL5_(OC5C)_40") (pintype "bidirectional"))
    )
    (net (code "67") (name "/PL6") (class "Default")
      (node (ref "TP119") (pin "1") (pinfunction "1_1") (pintype "passive"))
      (node (ref "U1") (pin "41") (pinfunction "PL6_41") (pintype "bidirectional"))
    )
    (net (code "68") (name "/PL7") (class "Default")
      (node (ref "TP120") (pin "1") (pinfunction "1_1") (pintype "passive"))
      (node (ref "U1") (pin "42") (pinfunction "PL7_42") (pintype "bidirectional"))
    )
    (net (code "69") (name "/RXD1") (class "Default")
      (node (ref "U1") (pin "45") (pinfunction "PD2_(RXD1/INT2)_45") (pintype "bidirectional"))
    )
    (net (code "70") (name "/RXD2") (class "Default")
      (node (ref "U1") (pin "12") (pinfunction "PH0_(RXD2)_12") (pintype "bidirectional"))
      (node (ref "U16") (pin "2") (pinfunction "I2_2") (pintype "passive"))
    )
    (net (code "71") (name "/RXD2_O") (class "Default")
      (node (ref "J1") (pin "3") (pinfunction "3_3") (pintype "passive"))
      (node (ref "U16") (pin "11") (pinfunction "O2_11") (pintype "passive"))
    )
    (net (code "72") (name "/RXD3") (class "Default")
      (node (ref "U1") (pin "63") (pinfunction "PJ0_(RXD3/PCINT9)_63") (pintype "bidirectional"))
    )
    (net (code "73") (name "/SCK (PB1)") (class "Default")
      (node (ref "J1") (pin "7") (pinfunction "7_7") (pintype "passive"))
      (node (ref "TP3") (pin "1") (pinfunction "1_1") (pintype "passive"))
      (node (ref "U16") (pin "8") (pinfunction "O5_8") (pintype "passive"))
    )
    (net (code "74") (name "/SCL") (class "Default")
      (node (ref "R2") (pin "1") (pinfunction "1_1") (pintype "passive"))
      (node (ref "U1") (pin "43") (pinfunction "PD0_(SCL/INT0)_43") (pintype "bidirectional"))
      (node (ref "U15") (pin "1") (pinfunction "D1_1") (pintype "passive"))
      (node (ref "U17") (pin "1") (pinfunction "D1_1") (pintype "passive"))
    )
    (net (code "75") (name "/SCL_O") (class "Default")
      (node (ref "P2") (pin "3") (pinfunction "3_3") (pintype "passive"))
      (node (ref "P5") (pin "3") (pinfunction "3_3") (pintype "passive"))
      (node (ref "U15") (pin "3") (pinfunction "O1_3") (pintype "passive"))
    )
    (net (code "76") (name "/SCL_O2") (class "Default")
      (node (ref "P4") (pin "8") (pinfunction "8_8") (pintype "passive"))
      (node (ref "U17") (pin "3") (pinfunction "O1_3") (pintype "passive"))
    )
    (net (code "77") (name "/SDA") (class "Default")
      (node (ref "R1") (pin "1") (pinfunction "1_1") (pintype "passive"))
      (node (ref "U1") (pin "44") (pinfunction "PD1_(SDA/INT1)_44") (pintype "bidirectional"))
      (node (ref "U15") (pin "6") (pinfunction "D2_6") (pintype "passive"))
      (node (ref "U17") (pin "6") (pinfunction "D2_6") (pintype "passive"))
    )
    (net (code "78") (name "/SDA_O") (class "Default")
      (node (ref "P2") (pin "4") (pinfunction "4_4") (pintype "passive"))
      (node (ref "P5") (pin "4") (pinfunction "4_4") (pintype "passive"))
      (node (ref "U15") (pin "4") (pinfunction "O2_4") (pintype "passive"))
    )
    (net (code "79") (name "/SDA_O2") (class "Default")
      (node (ref "P4") (pin "7") (pinfunction "7_7") (pintype "passive"))
      (node (ref "U17") (pin "4") (pinfunction "O2_4") (pintype "passive"))
    )
    (net (code "80") (name "/TXD1") (class "Default")
      (node (ref "U1") (pin "46") (pinfunction "PD3_(TXD1/INT3)_46") (pintype "bidirectional"))
    )
    (net (code "81") (name "/TXD2") (class "Default")
      (node (ref "U1") (pin "13") (pinfunction "PH1_(TXD2)_13") (pintype "bidirectional"))
      (node (ref "U16") (pin "1") (pinfunction "I1_1") (pintype "passive"))
    )
    (net (code "82") (name "/TXD2_O") (class "Default")
      (node (ref "J1") (pin "1") (pinfunction "1_1") (pintype "passive"))
      (node (ref "U16") (pin "12") (pinfunction "O1_12") (pintype "passive"))
    )
    (net (code "83") (name "/TXD3") (class "Default")
      (node (ref "U1") (pin "64") (pinfunction "PJ1_(TXD3/PCINT10)_64") (pintype "bidirectional"))
    )
    (net (code "84") (name "/nRESET") (class "Default")
      (node (ref "C1") (pin "2") (pinfunction "2_2") (pintype "passive"))
      (node (ref "C11") (pin "1") (pinfunction "1_1") (pintype "passive"))
      (node (ref "D1") (pin "1") (pinfunction "A_1") (pintype "passive"))
      (node (ref "JP2") (pin "1") (pinfunction "1_1") (pintype "passive"))
      (node (ref "JP2") (pin "2") (pinfunction "2_2") (pintype "passive"))
      (node (ref "R3") (pin "1") (pinfunction "1_1") (pintype "passive"))
      (node (ref "U1") (pin "30") (pinfunction "~{RESET}_30") (pintype "input"))
      (node (ref "U16") (pin "6") (pinfunction "I6_6") (pintype "passive"))
    )
    (net (code "85") (name "/nRESET_O") (class "Default")
      (node (ref "J1") (pin "9") (pinfunction "9_9") (pintype "passive"))
      (node (ref "TP1") (pin "1") (pinfunction "1_1") (pintype "passive"))
      (node (ref "U16") (pin "7") (pinfunction "O6_7") (pintype "passive"))
    )
    (net (code "86") (name "GND") (class "Default")
      (node (ref "C1") (pin "1") (pinfunction "1_1") (pintype "passive"))
      (node (ref "C10") (pin "1") (pinfunction "1_1") (pintype "passive"))
      (node (ref "C2") (pin "1") (pinfunction "1_1") (pintype "passive"))
      (node (ref "C3") (pin "1") (pinfunction "1_1") (pintype "passive"))
      (node (ref "C34") (pin "2") (pinfunction "2_2") (pintype "passive"))
      (node (ref "C4") (pin "1") (pinfunction "1_1") (pintype "passive"))
      (node (ref "C5") (pin "1") (pinfunction "1_1") (pintype "passive"))
      (node (ref "C6") (pin "1") (pinfunction "1_1") (pintype "passive"))
      (node (ref "C7") (pin "1") (pinfunction "1_1") (pintype "passive"))
      (node (ref "C8") (pin "1") (pinfunction "1_1") (pintype "passive"))
      (node (ref "C9") (pin "1") (pinfunction "1_1") (pintype "passive"))
      (node (ref "C91") (pin "1") (pinfunction "1_1") (pintype "passive"))
      (node (ref "D5") (pin "2") (pinfunction "A_2") (pintype "passive"))
      (node (ref "D6") (pin "2") (pinfunction "A_2") (pintype "passive"))
      (node (ref "J1") (pin "10") (pinfunction "10_10") (pintype "passive"))
      (node (ref "J1") (pin "2") (pinfunction "2_2") (pintype "passive"))
      (node (ref "J1") (pin "4") (pinfunction "4_4") (pintype "passive"))
      (node (ref "J2") (pin "6") (pinfunction "6_6") (pintype "passive"))
      (node (ref "J23") (pin "1") (pinfunction "1_1") (pintype "passive"))
      (node (ref "J23") (pin "2") (pinfunction "2_2") (pintype "passive"))
      (node (ref "J3") (pin "4") (pinfunction "4_4") (pintype "passive"))
      (node (ref "P2") (pin "2") (pinfunction "2_2") (pintype "passive"))
      (node (ref "P4") (pin "10") (pinfunction "10_10") (pintype "passive"))
      (node (ref "P4") (pin "6") (pinfunction "6_6") (pintype "passive"))
      (node (ref "P5") (pin "2") (pinfunction "2_2") (pintype "passive"))
      (node (ref "R116") (pin "1") (pinfunction "1_1") (pintype "passive"))
      (node (ref "R117") (pin "1") (pinfunction "1_1") (pintype "passive"))
      (node (ref "R118") (pin "1") (pinfunction "1_1") (pintype "passive"))
      (node (ref "R119") (pin "1") (pinfunction "1_1") (pintype "passive"))
      (node (ref "R121") (pin "2") (pinfunction "2_2") (pintype "passive"))
      (node (ref "R15") (pin "2") (pinfunction "2_2") (pintype "passive"))
      (node (ref "TP12") (pin "1") (pinfunction "1_1") (pintype "passive"))
      (node (ref "U1") (pin "11") (pinfunction "GND_11") (pintype "power_in"))
      (node (ref "U1") (pin "32") (pinfunction "GND_32") (pintype "power_in"))
      (node (ref "U1") (pin "62") (pinfunction "GND_62") (pintype "power_in"))
      (node (ref "U1") (pin "81") (pinfunction "GND_81") (pintype "power_in"))
      (node (ref "U1") (pin "99") (pinfunction "AGND_99") (pintype "power_in"))
      (node (ref "U15") (pin "2") (pinfunction "GND_2") (pintype "passive"))
      (node (ref "U15") (pin "5") (pinfunction "GND_5") (pintype "passive"))
      (node (ref "U16") (pin "13") (pinfunction "GND_13") (pintype "passive"))
      (node (ref "U17") (pin "2") (pinfunction "GND_2") (pintype "passive"))
      (node (ref "U17") (pin "5") (pinfunction "GND_5") (pintype "passive"))
      (node (ref "U2") (pin "28") (pinfunction "UGND_28") (pintype "passive"))
      (node (ref "U2") (pin "3") (pinfunction "GND_3") (pintype "passive"))
      (node (ref "U2") (pin "EXPAD") (pintype "passive"))
      (node (ref "Y1") (pin "2") (pinfunction "2_2") (pintype "passive"))
    )
    (net (code "87") (name "Net-(C34-Pad1)") (class "Default")
      (node (ref "C34") (pin "1") (pinfunction "1_1") (pintype "passive"))
      (node (ref "J3") (pin "5") (pinfunction "5_5") (pintype "passive"))
      (node (ref "R121") (pin "1") (pinfunction "1_1") (pintype "passive"))
      (node (ref "R8") (pin "1") (pinfunction "1_1") (pintype "passive"))
      (node (ref "R9") (pin "1") (pinfunction "1_1") (pintype "passive"))
      (node (ref "TP168") (pin "1") (pinfunction "1_1") (pintype "passive"))
    )
    (net (code "88") (name "Net-(D2-A)") (class "Default")
      (node (ref "D2") (pin "1") (pinfunction "A_1") (pintype "passive"))
      (node (ref "J2") (pin "5") (pinfunction "5_5") (pintype "passive"))
      (node (ref "R5") (pin "2") (pinfunction "2_2") (pintype "passive"))
      (node (ref "TP8") (pin "1") (pinfunction "1_1") (pintype "passive"))
      (node (ref "U2") (pin "24") (pinfunction "~{RESET}_(PC1_/_dW)_24") (pintype "passive"))
    )
    (net (code "89") (name "Net-(D3-A)") (class "Default")
      (node (ref "D3") (pin "1") (pinfunction "A_1") (pintype "passive"))
      (node (ref "R11") (pin "1") (pinfunction "1_1") (pintype "passive"))
      (node (ref "TP180") (pin "1") (pinfunction "1_1") (pintype "passive"))
    )
    (net (code "90") (name "Net-(D3-K)") (class "Default")
      (node (ref "D3") (pin "2") (pinfunction "K_2") (pintype "passive"))
      (node (ref "TP179") (pin "1") (pinfunction "1_1") (pintype "passive"))
      (node (ref "U2") (pin "10") (pinfunction "PD4_(INT5_/_AIN3)_10") (pintype "passive"))
    )
    (net (code "91") (name "Net-(D4-A)") (class "Default")
      (node (ref "D4") (pin "1") (pinfunction "A_1") (pintype "passive"))
      (node (ref "R12") (pin "1") (pinfunction "1_1") (pintype "passive"))
      (node (ref "TP189") (pin "1") (pinfunction "1_1") (pintype "passive"))
    )
    (net (code "92") (name "Net-(D4-K)") (class "Default")
      (node (ref "D4") (pin "2") (pinfunction "K_2") (pintype "passive"))
      (node (ref "TP190") (pin "1") (pinfunction "1_1") (pintype "passive"))
      (node (ref "U2") (pin "11") (pinfunction "PD5_(XCK_/_AIN4_/_PCINT12)_11") (pintype "passive"))
    )
    (net (code "93") (name "Net-(F1-Pad1)") (class "Default")
      (node (ref "F1") (pin "1") (pinfunction "1_1") (pintype "passive"))
      (node (ref "J3") (pin "1") (pinfunction "1_1") (pintype "passive"))
      (node (ref "TP9") (pin "1") (pinfunction "1_1") (pintype "passive"))
    )
    (net (code "94") (name "Net-(J3-Pad2)") (class "Default")
      (node (ref "J3") (pin "2") (pinfunction "2_2") (pintype "passive"))
      (node (ref "R6") (pin "1") (pinfunction "1_1") (pintype "passive"))
      (node (ref "R8") (pin "2") (pinfunction "2_2") (pintype "passive"))
      (node (ref "TP10") (pin "1") (pinfunction "1_1") (pintype "passive"))
    )
    (net (code "95") (name "Net-(J3-Pad3)") (class "Default")
      (node (ref "J3") (pin "3") (pinfunction "3_3") (pintype "passive"))
      (node (ref "R7") (pin "1") (pinfunction "1_1") (pintype "passive"))
      (node (ref "R9") (pin "2") (pinfunction "2_2") (pintype "passive"))
      (node (ref "TP11") (pin "1") (pinfunction "1_1") (pintype "passive"))
    )
    (net (code "96") (name "Net-(R116-Pad2)") (class "Default")
      (node (ref "R116") (pin "2") (pinfunction "2_2") (pintype "passive"))
      (node (ref "SP1") (pin "1") (pinfunction "1_1") (pintype "passive"))
    )
    (net (code "97") (name "Net-(R117-Pad2)") (class "Default")
      (node (ref "R117") (pin "2") (pinfunction "2_2") (pintype "passive"))
      (node (ref "SP2") (pin "1") (pinfunction "1_1") (pintype "passive"))
    )
    (net (code "98") (name "Net-(R118-Pad2)") (class "Default")
      (node (ref "R118") (pin "2") (pinfunction "2_2") (pintype "passive"))
      (node (ref "SP3") (pin "1") (pinfunction "1_1") (pintype "passive"))
    )
    (net (code "99") (name "Net-(R119-Pad2)") (class "Default")
      (node (ref "R119") (pin "2") (pinfunction "2_2") (pintype "passive"))
      (node (ref "SP4") (pin "1") (pinfunction "1_1") (pintype "passive"))
    )
    (net (code "100") (name "Net-(U1-XTAL1)") (class "Default")
      (node (ref "R4") (pin "2") (pinfunction "2_2") (pintype "passive"))
      (node (ref "TP130") (pin "1") (pinfunction "1_1") (pintype "passive"))
      (node (ref "U1") (pin "34") (pinfunction "XTAL1_34") (pintype "input"))
      (node (ref "Y1") (pin "1") (pinfunction "1_1") (pintype "passive"))
    )
    (net (code "101") (name "Net-(U1-XTAL2)") (class "Default")
      (node (ref "R4") (pin "1") (pinfunction "1_1") (pintype "passive"))
      (node (ref "TP131") (pin "1") (pinfunction "1_1") (pintype "passive"))
      (node (ref "U1") (pin "33") (pinfunction "XTAL2_33") (pintype "output"))
      (node (ref "Y1") (pin "3") (pinfunction "3_3") (pintype "passive"))
    )
    (net (code "102") (name "Net-(U2-D+)") (class "Default")
      (node (ref "R7") (pin "2") (pinfunction "2_2") (pintype "passive"))
      (node (ref "TP170") (pin "1") (pinfunction "1_1") (pintype "passive"))
      (node (ref "U2") (pin "29") (pinfunction "D+_29") (pintype "passive"))
    )
    (net (code "103") (name "Net-(U2-D-)") (class "Default")
      (node (ref "R6") (pin "2") (pinfunction "2_2") (pintype "passive"))
      (node (ref "TP169") (pin "1") (pinfunction "1_1") (pintype "passive"))
      (node (ref "U2") (pin "30") (pinfunction "D-_30") (pintype "passive"))
    )
    (net (code "104") (name "Net-(U2-PB0_(~{SS}_{slash}_PCINT0))") (class "Default")
      (node (ref "O2") (pin "2") (pinfunction "2_2") (pintype "passive"))
      (node (ref "TP86") (pin "1") (pinfunction "1_1") (pintype "passive"))
      (node (ref "U2") (pin "14") (pinfunction "PB0_(~{SS}_/_PCINT0)_14") (pintype "passive"))
    )
    (net (code "105") (name "Net-(U2-PB1_(SCLK_{slash}_PCINT1))") (class "Default")
      (node (ref "J2") (pin "3") (pinfunction "3_3") (pintype "passive"))
      (node (ref "TP6") (pin "1") (pinfunction "1_1") (pintype "passive"))
      (node (ref "U2") (pin "15") (pinfunction "PB1_(SCLK_/_PCINT1)_15") (pintype "passive"))
    )
    (net (code "106") (name "Net-(U2-PB2_(PDI_{slash}_MOSI_{slash}_PCINT2))") (class "Default")
      (node (ref "J2") (pin "4") (pinfunction "4_4") (pintype "passive"))
      (node (ref "TP7") (pin "1") (pinfunction "1_1") (pintype "passive"))
      (node (ref "U2") (pin "16") (pinfunction "PB2_(PDI_/_MOSI_/_PCINT2)_16") (pintype "passive"))
    )
    (net (code "107") (name "Net-(U2-PB3_(PDO_{slash}_MISO_{slash}_PCINT3))") (class "Default")
      (node (ref "J2") (pin "1") (pinfunction "1_1") (pintype "passive"))
      (node (ref "TP5") (pin "1") (pinfunction "1_1") (pintype "passive"))
      (node (ref "U2") (pin "17") (pinfunction "PB3_(PDO_/_MISO_/_PCINT3)_17") (pintype "passive"))
    )
    (net (code "108") (name "Net-(U2-PB4_(T1_{slash}_PCINT4))") (class "Default")
      (node (ref "J4") (pin "1") (pinfunction "1_1") (pintype "passive"))
      (node (ref "TP66") (pin "1") (pinfunction "1_1") (pintype "passive"))
      (node (ref "U2") (pin "18") (pinfunction "PB4_(T1_/_PCINT4)_18") (pintype "passive"))
    )
    (net (code "109") (name "Net-(U2-PB5_(PCINT5))") (class "Default")
      (node (ref "J4") (pin "3") (pinfunction "3_3") (pintype "passive"))
      (node (ref "TP68") (pin "1") (pinfunction "1_1") (pintype "passive"))
      (node (ref "U2") (pin "19") (pinfunction "PB5_(PCINT5)_19") (pintype "passive"))
    )
    (net (code "110") (name "Net-(U2-PB6_(PCINT6))") (class "Default")
      (node (ref "J4") (pin "2") (pinfunction "2_2") (pintype "passive"))
      (node (ref "TP67") (pin "1") (pinfunction "1_1") (pintype "passive"))
      (node (ref "U2") (pin "20") (pinfunction "PB6_(PCINT6)_20") (pintype "passive"))
    )
    (net (code "111") (name "Net-(U2-PB7_(PCINT7_{slash}_OC.0A_{slash}_OC.1C))") (class "Default")
      (node (ref "J4") (pin "4") (pinfunction "4_4") (pintype "passive"))
      (node (ref "TP69") (pin "1") (pinfunction "1_1") (pintype "passive"))
      (node (ref "U2") (pin "21") (pinfunction "PB7_(PCINT7_/_OC.0A_/_OC.1C)_21") (pintype "passive"))
    )
    (net (code "112") (name "Net-(U2-PD2_(RXD1_{slash}_AIN1_{slash}_INT2))") (class "Default")
      (node (ref "R13") (pin "1") (pinfunction "1_1") (pintype "passive"))
      (node (ref "TP174") (pin "1") (pinfunction "1_1") (pintype "passive"))
      (node (ref "U2") (pin "8") (pinfunction "PD2_(RXD1_/_AIN1_/_INT2)_8") (pintype "passive"))
    )
    (net (code "113") (name "Net-(U2-PD3_(TXD1_{slash}_INT3))") (class "Default")
      (node (ref "R14") (pin "1") (pinfunction "1_1") (pintype "passive"))
      (node (ref "TP175") (pin "1") (pinfunction "1_1") (pintype "passive"))
      (node (ref "U2") (pin "9") (pinfunction "PD3_(TXD1_/_INT3)_9") (pintype "passive"))
    )
    (net (code "114") (name "Net-(U2-PD7_(~{CTS}_{slash}_~{HWB}_{slash}_AIN6_{slash}_T0_{slash}_INT7))") (class "Default")
      (node (ref "C11") (pin "2") (pinfunction "2_2") (pintype "passive"))
      (node (ref "R15") (pin "1") (pinfunction "1_1") (pintype "passive"))
      (node (ref "TP178") (pin "1") (pinfunction "1_1") (pintype "passive"))
      (node (ref "U2") (pin "13") (pinfunction "PD7_(~{CTS}_/_~{HWB}_/_AIN6_/_T0_/_INT7)_13") (pintype "passive"))
    )
    (net (code "115") (name "Net-(U2-UCAP)") (class "Default")
      (node (ref "C6") (pin "2") (pinfunction "2_2") (pintype "passive"))
      (node (ref "TP171") (pin "1") (pinfunction "1_1") (pintype "passive"))
      (node (ref "U2") (pin "27") (pinfunction "UCAP_27") (pintype "passive"))
    )
    (net (code "116") (name "Net-(U2-UVCC)") (class "Default")
      (node (ref "C8") (pin "2") (pinfunction "2_2") (pintype "passive"))
      (node (ref "F1") (pin "2") (pinfunction "2_2") (pintype "passive"))
      (node (ref "TP167") (pin "1") (pinfunction "1_1") (pintype "passive"))
      (node (ref "U2") (pin "31") (pinfunction "UVCC_31") (pintype "passive"))
    )
    (net (code "117") (name "Net-(U2-XTAL1)") (class "Default")
      (node (ref "C7") (pin "2") (pinfunction "2_2") (pintype "passive"))
      (node (ref "R10") (pin "2") (pinfunction "2_2") (pintype "passive"))
      (node (ref "TP172") (pin "1") (pinfunction "1_1") (pintype "passive"))
      (node (ref "U2") (pin "1") (pinfunction "XTAL1_1") (pintype "passive"))
      (node (ref "Y2") (pin "2") (pinfunction "2_2") (pintype "passive"))
    )
    (net (code "118") (name "Net-(U2-XTAL2_(PC0))") (class "Default")
      (node (ref "C9") (pin "2") (pinfunction "2_2") (pintype "passive"))
      (node (ref "R10") (pin "1") (pinfunction "1_1") (pintype "passive"))
      (node (ref "TP173") (pin "1") (pinfunction "1_1") (pintype "passive"))
      (node (ref "U2") (pin "2") (pinfunction "XTAL2_(PC0)_2") (pintype "passive"))
      (node (ref "Y2") (pin "1") (pinfunction "1_1") (pintype "passive"))
    )
    (net (code "119") (name "unconnected-(TP107-Pad1)") (class "Default")
      (node (ref "TP107") (pin "1") (pinfunction "1_1") (pintype "passive"))
    )
    (net (code "120") (name "unconnected-(TP108-Pad1)") (class "Default")
      (node (ref "TP108") (pin "1") (pinfunction "1_1") (pintype "passive"))
    )
    (net (code "121") (name "unconnected-(U1-PB4_(OC2A{slash}PCINT4)-Pad23)") (class "Default")
      (node (ref "U1") (pin "23") (pinfunction "PB4_(OC2A/PCINT4)_23") (pintype "bidirectional"))
    )
    (net (code "122") (name "unconnected-(U1-PB5_(OC1A{slash}PCINT5)-Pad24)") (class "Default")
      (node (ref "U1") (pin "24") (pinfunction "PB5_(OC1A/PCINT5)_24") (pintype "bidirectional"))
    )
    (net (code "123") (name "unconnected-(U1-PD4_(ICP1)-Pad47)") (class "Default")
      (node (ref "U1") (pin "47") (pinfunction "PD4_(ICP1)_47") (pintype "bidirectional"))
    )
    (net (code "124") (name "unconnected-(U1-PD5_(XCK1)-Pad48)") (class "Default")
      (node (ref "U1") (pin "48") (pinfunction "PD5_(XCK1)_48") (pintype "bidirectional"))
    )
    (net (code "125") (name "unconnected-(U1-PD6_(T1)-Pad49)") (class "Default")
      (node (ref "U1") (pin "49") (pinfunction "PD6_(T1)_49") (pintype "bidirectional"))
    )
    (net (code "126") (name "unconnected-(U1-PE2_(XCK0{slash}AIN0)-Pad4)") (class "Default")
      (node (ref "U1") (pin "4") (pinfunction "PE2_(XCK0/AIN0)_4") (pintype "bidirectional"))
    )
    (net (code "127") (name "unconnected-(U1-PE6_(T3{slash}INT6)-Pad8)") (class "Default")
      (node (ref "U1") (pin "8") (pinfunction "PE6_(T3/INT6)_8") (pintype "bidirectional"))
    )
    (net (code "128") (name "unconnected-(U1-PE7_(CLKO{slash}ICP3{slash}INT7)-Pad9)") (class "Default")
      (node (ref "U1") (pin "9") (pinfunction "PE7_(CLKO/ICP3/INT7)_9") (pintype "bidirectional"))
    )
    (net (code "129") (name "unconnected-(U1-PG3_(TOSC2)-Pad28)") (class "Default")
      (node (ref "U1") (pin "28") (pinfunction "PG3_(TOSC2)_28") (pintype "bidirectional"))
    )
    (net (code "130") (name "unconnected-(U1-PG4_(TOSC1)-Pad29)") (class "Default")
      (node (ref "U1") (pin "29") (pinfunction "PG4_(TOSC1)_29") (pintype "bidirectional"))
    )
    (net (code "131") (name "unconnected-(U1-PH2_(XCK2)-Pad14)") (class "Default")
      (node (ref "U1") (pin "14") (pinfunction "PH2_(XCK2)_14") (pintype "bidirectional"))
    )
    (net (code "132") (name "unconnected-(U1-PH6_(OC2B)-Pad18)") (class "Default")
      (node (ref "U1") (pin "18") (pinfunction "PH6_(OC2B)_18") (pintype "bidirectional"))
    )
    (net (code "133") (name "unconnected-(U1-PH7_(T4)-Pad27)") (class "Default")
      (node (ref "U1") (pin "27") (pinfunction "PH7_(T4)_27") (pintype "bidirectional"))
    )
    (net (code "134") (name "unconnected-(U1-PJ2_(XCK3{slash}PCINT11)-Pad65)") (class "Default")
      (node (ref "U1") (pin "65") (pinfunction "PJ2_(XCK3/PCINT11)_65") (pintype "bidirectional"))
    )
    (net (code "135") (name "unconnected-(U1-PJ3_(PCINT12)-Pad66)") (class "Default")
      (node (ref "U1") (pin "66") (pinfunction "PJ3_(PCINT12)_66") (pintype "bidirectional"))
    )
    (net (code "136") (name "unconnected-(U1-PJ4_(PCINT13)-Pad67)") (class "Default")
      (node (ref "U1") (pin "67") (pinfunction "PJ4_(PCINT13)_67") (pintype "bidirectional"))
    )
    (net (code "137") (name "unconnected-(U1-PJ5_(PCINT14)-Pad68)") (class "Default")
      (node (ref "U1") (pin "68") (pinfunction "PJ5_(PCINT14)_68") (pintype "bidirectional"))
    )
    (net (code "138") (name "unconnected-(U1-PJ7-Pad79)") (class "Default")
      (node (ref "U1") (pin "79") (pinfunction "PJ7_79") (pintype "bidirectional"))
    )
    (net (code "139") (name "unconnected-(U2-PC2_(PCINT11_{slash}_AIN2)-Pad5)") (class "Default")
      (node (ref "U2") (pin "5") (pinfunction "PC2_(PCINT11_/_AIN2)_5") (pintype "passive"))
    )
    (net (code "140") (name "unconnected-(U2-PC4_(PCINT10)-Pad26)") (class "Default")
      (node (ref "U2") (pin "26") (pinfunction "PC4_(PCINT10)_26") (pintype "passive"))
    )
    (net (code "141") (name "unconnected-(U2-PC5_(PCINT9_{slash}_OC.1B)-Pad25)") (class "Default")
      (node (ref "U2") (pin "25") (pinfunction "PC5_(PCINT9_/_OC.1B)_25") (pintype "passive"))
    )
    (net (code "142") (name "unconnected-(U2-PC6_(OC.1A_{slash}_PCINT8)-Pad23)") (class "Default")
      (node (ref "U2") (pin "23") (pinfunction "PC6_(OC.1A_/_PCINT8)_23") (pintype "passive"))
    )
    (net (code "143") (name "unconnected-(U2-PC7_(INT4_{slash}_ICP1_{slash}_CLKO)-Pad22)") (class "Default")
      (node (ref "U2") (pin "22") (pinfunction "PC7_(INT4_/_ICP1_/_CLKO)_22") (pintype "passive"))
    )
    (net (code "144") (name "unconnected-(U2-PD0_(OC.0B_{slash}_INT0)-Pad6)") (class "Default")
      (node (ref "U2") (pin "6") (pinfunction "PD0_(OC.0B_/_INT0)_6") (pintype "passive"))
    )
    (net (code "145") (name "unconnected-(U2-PD1_(AIN0_{slash}_INT1)-Pad7)") (class "Default")
      (node (ref "U2") (pin "7") (pinfunction "PD1_(AIN0_/_INT1)_7") (pintype "passive"))
    )
  )
)
